# CCM_0017.net
KiCad netlist of a schematic drawn in EAGLE
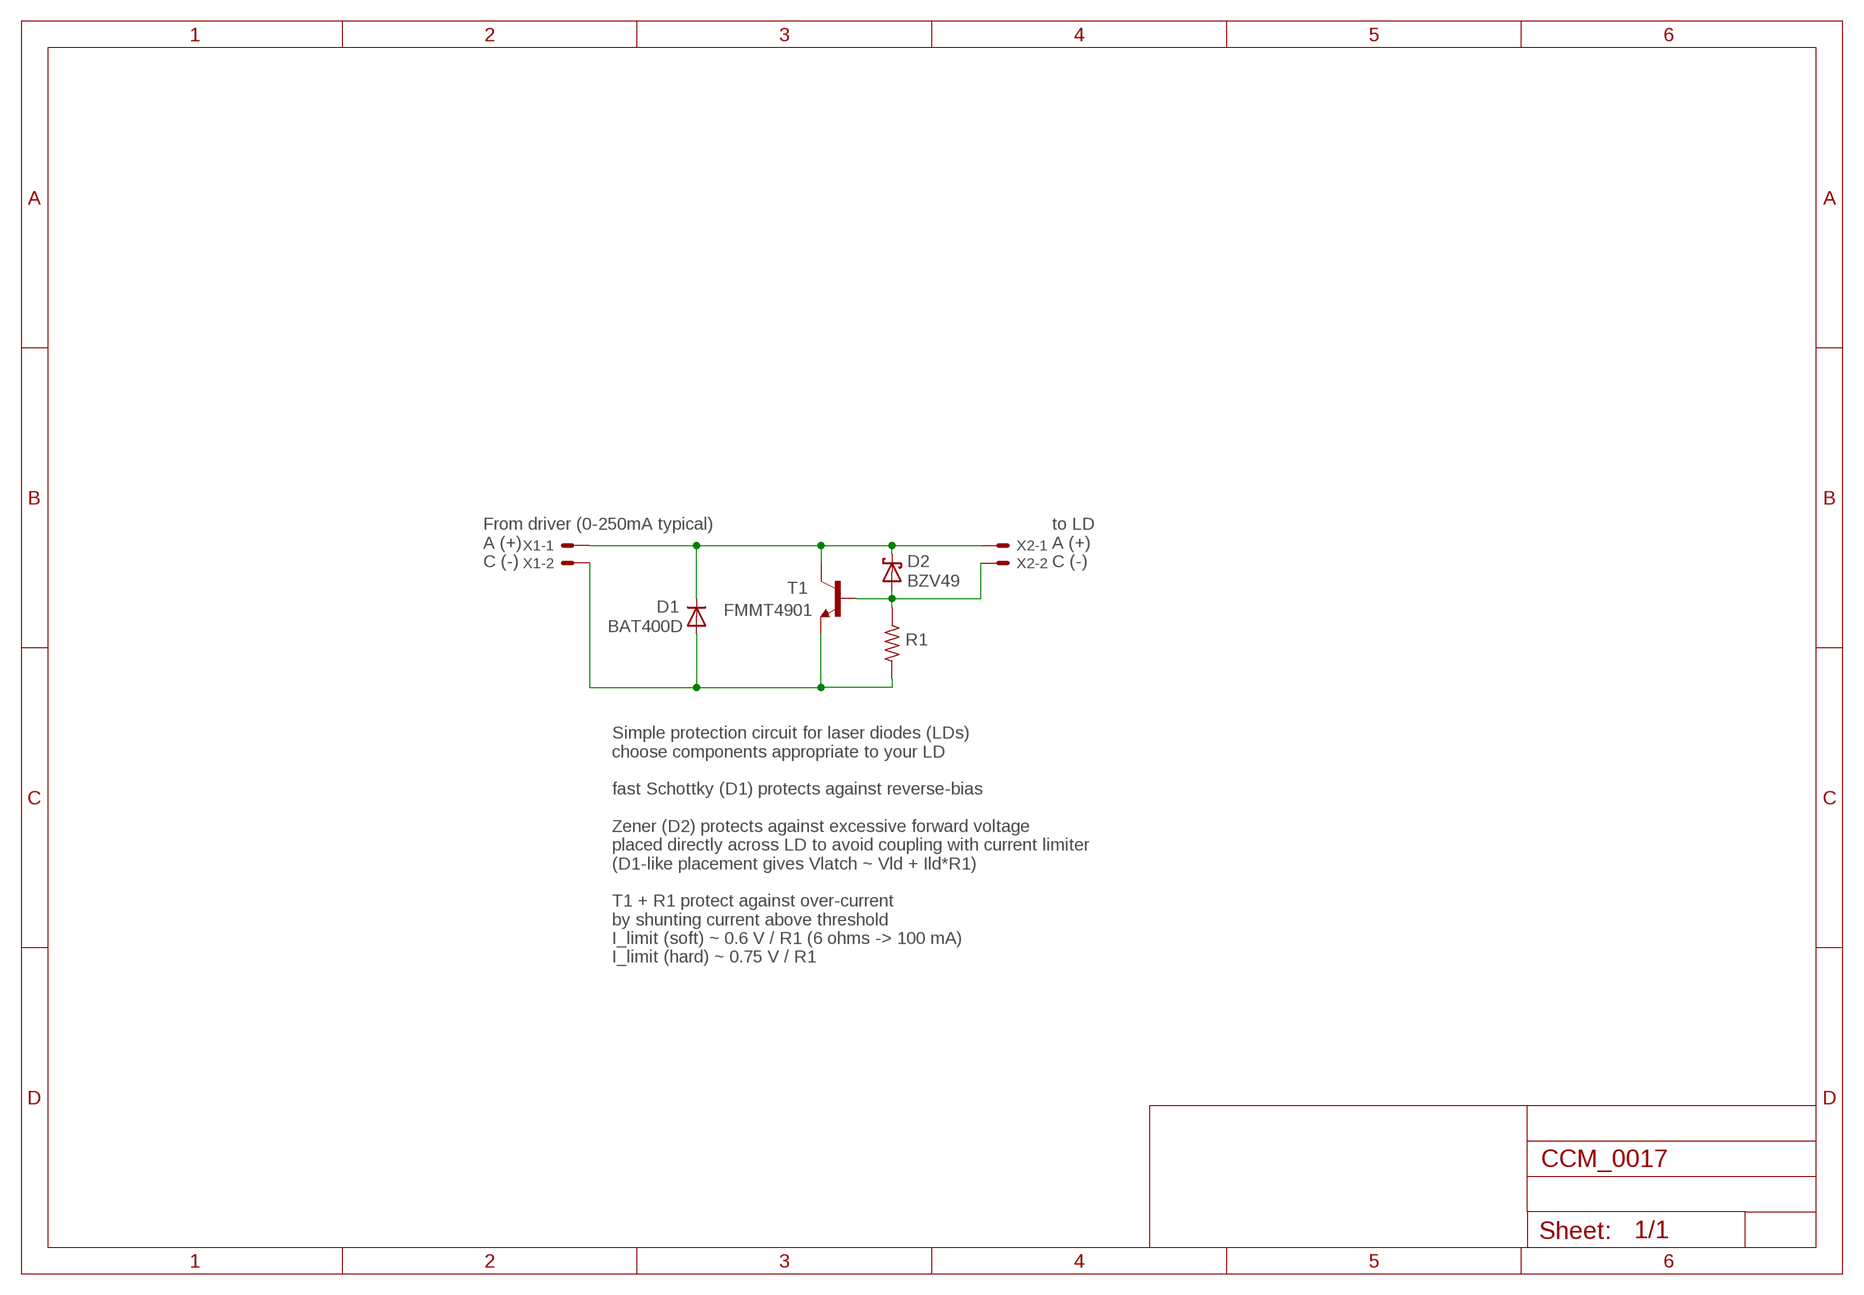
[diagram p0: schematic, sheet 1]

(export (version "E")
  (design (tool "Eeschema 10.0.6"))
  (components
    (comp (ref "D1")
      (value "BAT400D")
      (footprint "eagle-import:SOT23")
      (libsource (lib "eagle-import") (part "HSMS-2850"))
    )
    (comp (ref "D2")
      (value "BZV49")
      (footprint "eagle-import:SOT89")
      (libsource (lib "eagle-import") (part "BZV49"))
    )
    (comp (ref "R1")
      (value "4.3")
      (footprint "eagle-import:1210")
      (libsource (lib "eagle-import") (part "RESISTOR1210"))
    )
    (comp (ref "T1")
      (value "FMMT4901")
      (footprint "eagle-import:SOT23-BEC")
      (libsource (lib "eagle-import") (part "-NPN-SOT23-BECMMBT4401LT1"))
    )
    (comp (ref "X1")
      (value "22-23-2021")
      (footprint "eagle-import:22-23-2021")
      (fields (field (name "MF") "MOLEX"))
      (libsource (lib "eagle-import") (part "22-23-2021"))
    )
    (comp (ref "X2")
      (value "22-23-2021")
      (footprint "eagle-import:22-23-2021")
      (fields (field (name "MF") "MOLEX"))
      (libsource (lib "eagle-import") (part "22-23-2021"))
    )
  )
  (nets
    (net (code "1") (name "Net-(D1-A)") (class "Default")
      (node (ref "D1") (pin "1") (pinfunction "A_1") (pintype "passive"))
      (node (ref "R1") (pin "2") (pinfunction "2_2") (pintype "passive"))
      (node (ref "T1") (pin "E") (pinfunction "E_E") (pintype "passive"))
      (node (ref "X1") (pin "2") (pinfunction "S_2") (pintype "passive"))
    )
    (net (code "2") (name "Net-(D1-C)") (class "Default")
      (node (ref "D1") (pin "3") (pinfunction "C_3") (pintype "passive"))
      (node (ref "D2") (pin "2") (pinfunction "C_2") (pintype "passive"))
      (node (ref "D2") (pin "2@1") (pinfunction "C_2@1") (pintype "passive"))
      (node (ref "T1") (pin "C") (pinfunction "C_C") (pintype "passive"))
      (node (ref "X1") (pin "1") (pinfunction "S_1") (pintype "passive"))
      (node (ref "X2") (pin "1") (pinfunction "S_1") (pintype "passive"))
    )
    (net (code "3") (name "Net-(X2B-S)") (class "Default")
      (node (ref "D2") (pin "1") (pinfunction "A_1") (pintype "passive"))
      (node (ref "D2") (pin "3") (pinfunction "A_3") (pintype "passive"))
      (node (ref "R1") (pin "1") (pinfunction "1_1") (pintype "passive"))
      (node (ref "T1") (pin "B") (pinfunction "B_B") (pintype "passive"))
      (node (ref "X2") (pin "2") (pinfunction "S_2") (pintype "passive"))
    )
  )
)
